# SUPI_MediumR2.net
KiCad netlist of a schematic drawn in Altium Designer
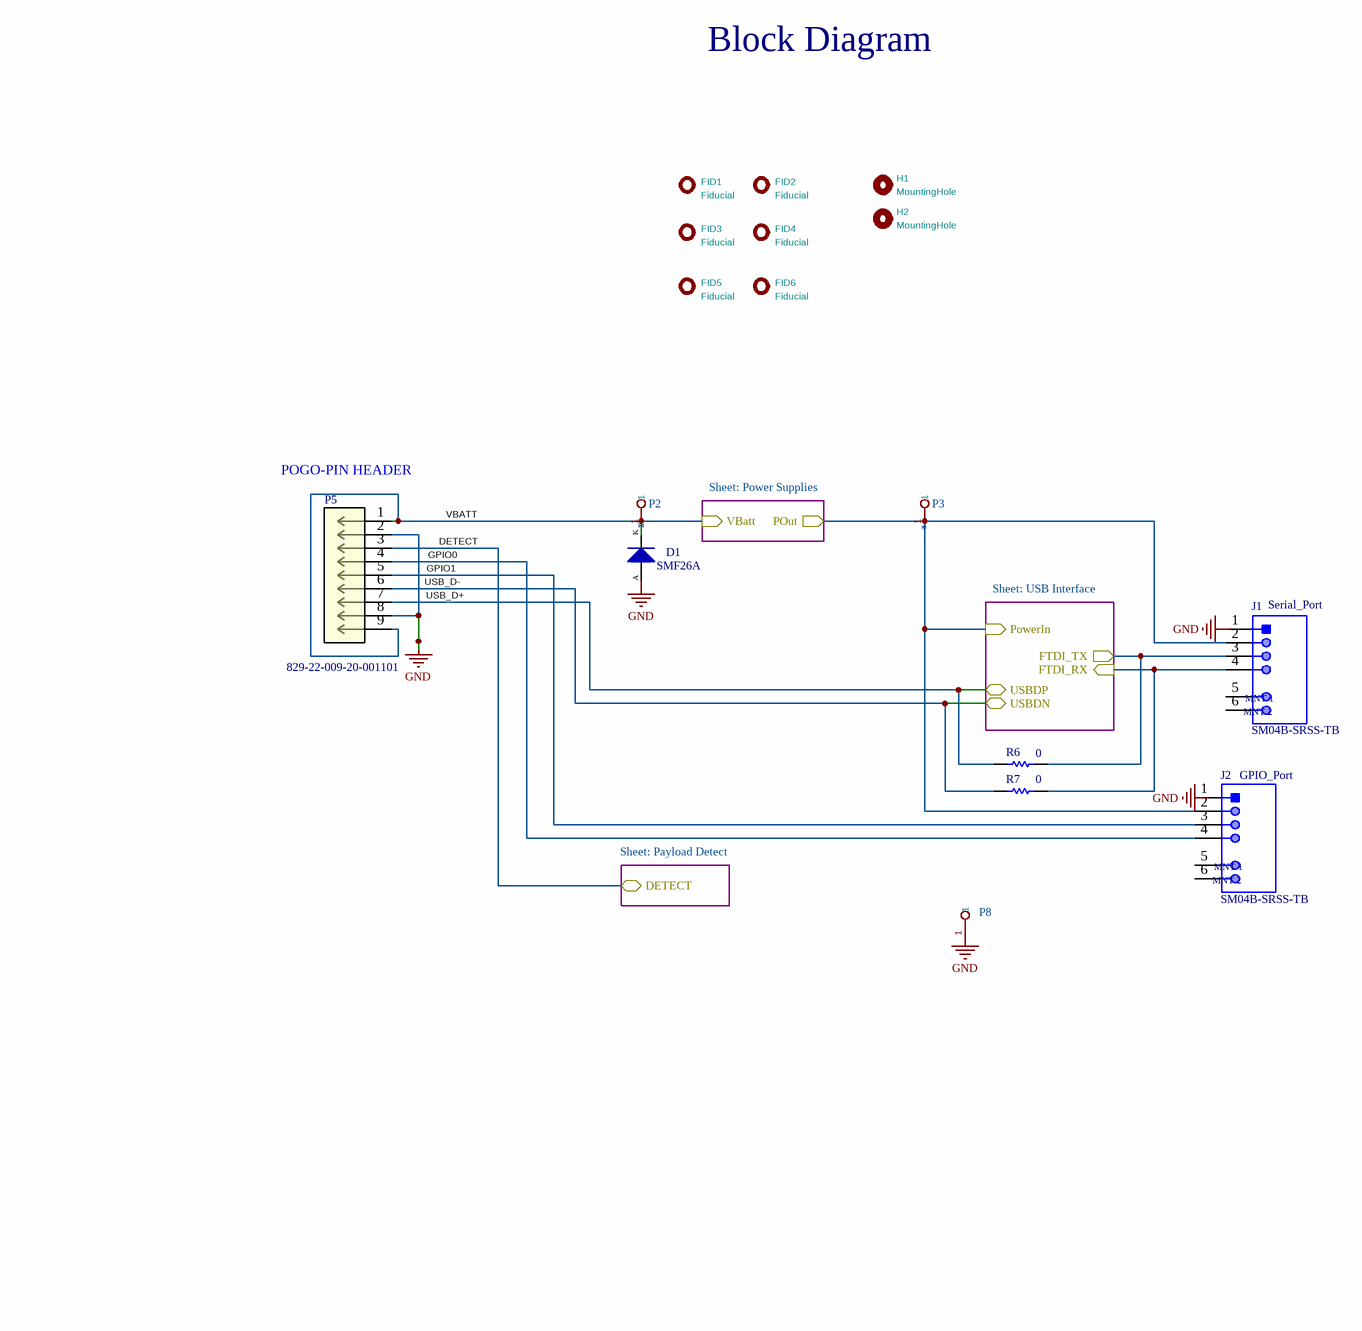
[diagram p0: SUPI_MediumR2.SchDoc]

(export (version "E")
  (design (tool "Eeschema 10.0.6"))
  (components
    (comp (ref "D1")
      (value "SMF26A")
      (footprint "DI-SOD123F-A")
      (description "SMF Series 200 W 26 V Uni-Directional Surface Mount TVS Diode - SOD-123F")
      (libsource (lib "Picatinny Server") (part "Diode"))
    )
    (comp (ref "FID1")
      (value "Fiducial")
      (footprint "Fiducial_Cu0.040_Mask0.060")
      (libsource (lib "1a_Misc") (part "Fiducial_40mil_mask_60mil"))
    )
    (comp (ref "FID2")
      (value "Fiducial")
      (footprint "Fiducial_Cu0.040_Mask0.060")
      (libsource (lib "1a_Misc") (part "Fiducial_40mil_mask_60mil"))
    )
    (comp (ref "FID3")
      (value "Fiducial")
      (footprint "Fiducial_Cu0.040_Mask0.060")
      (libsource (lib "1a_Misc") (part "Fiducial_40mil_mask_60mil"))
    )
    (comp (ref "FID4")
      (value "Fiducial")
      (footprint "Fiducial_Cu0.040_Mask0.060")
      (libsource (lib "1a_Misc") (part "Fiducial_40mil_mask_60mil"))
    )
    (comp (ref "FID5")
      (value "Fiducial")
      (footprint "Fiducial_Cu0.040_Mask0.060")
      (libsource (lib "1a_Misc") (part "Fiducial_40mil_mask_60mil"))
    )
    (comp (ref "FID6")
      (value "Fiducial")
      (footprint "Fiducial_Cu0.040_Mask0.060")
      (libsource (lib "1a_Misc") (part "Fiducial_40mil_mask_60mil"))
    )
    (comp (ref "H1")
      (value "MountingHole")
      (footprint "MountingHole_2.2mm_M2_DIN965")
      (libsource (lib "Mechanical") (part "MountingHole"))
    )
    (comp (ref "H2")
      (value "MountingHole")
      (footprint "MountingHole_2.2mm_M2_DIN965")
      (libsource (lib "Mechanical") (part "MountingHole"))
    )
    (comp (ref "J1")
      (value "SM04B-SRSS-TB")
      (footprint "SM04B-SRSS-TB")
      (description "Conn Shrouded Header (4 Sides) HDR 4 POS 1.25mm Solder RA Side Entry SMD T/R")
      (libsource (lib "Picatinny Server") (part "SM04B-GHS-TB"))
    )
    (comp (ref "J2")
      (value "SM04B-SRSS-TB")
      (footprint "SM04B-SRSS-TB")
      (description "Conn Shrouded Header (4 Sides) HDR 4 POS 1.25mm Solder RA Side Entry SMD T/R")
      (libsource (lib "Picatinny Server") (part "SM04B-GHS-TB"))
    )
    (comp (ref "P2")
      (value "*")
      (footprint "TP_SMD_1MM")
      (libsource (lib "1a_Misc") (part "Hand_Solder_Pad_100x80_mil"))
    )
    (comp (ref "P3")
      (value "*")
      (footprint "TP_SMD_1MM")
      (libsource (lib "1a_Misc") (part "Hand_Solder_Pad_100x80_mil"))
    )
    (comp (ref "P5")
      (value "829-22-009-20-001101")
      (footprint "829-22-009-20-001101")
      (description "Board Connector, 9 Contact(s), 1 Row(s), Male, Right Angle, Solder Terminal")
      (libsource (lib "Picatinny Server") (part "9 Pos Connector"))
    )
    (comp (ref "P8")
      (value "~")
      (footprint "TP_SMD_1MM")
      (libsource (lib "1a_Misc") (part "Hand_Solder_Pad_100x80_mil"))
    )
    (comp (ref "R6")
      (value "0")
      (footprint "RES-0402-A")
      (description "Res 0402 0 Ohm 1/16W 5% Thick Film")
      (libsource (lib "Picatinny Server") (part "Resistor"))
    )
    (comp (ref "R7")
      (value "0")
      (footprint "RES-0402-A")
      (description "Res 0402 0 Ohm 1/16W 5% Thick Film")
      (libsource (lib "Picatinny Server") (part "Resistor"))
    )
  )
  (nets
    (net (code "1") (name "/DETECT") (class "Default")
      (node (ref "P5") (pin "3") (pinfunction "3_3") (pintype "passive"))
    )
    (net (code "2") (name "/FTDI_RX") (class "Default")
      (node (ref "J1") (pin "4") (pinfunction "4_4") (pintype "passive"))
      (node (ref "R7") (pin "2") (pinfunction "2_2") (pintype "passive"))
    )
    (net (code "3") (name "/FTDI_TX") (class "Default")
      (node (ref "J1") (pin "3") (pinfunction "3_3") (pintype "passive"))
      (node (ref "R6") (pin "2") (pinfunction "2_2") (pintype "passive"))
    )
    (net (code "4") (name "/GPIO0") (class "Default")
      (node (ref "J2") (pin "4") (pinfunction "4_4") (pintype "passive"))
      (node (ref "P5") (pin "4") (pinfunction "4_4") (pintype "passive"))
    )
    (net (code "5") (name "/GPIO1") (class "Default")
      (node (ref "J2") (pin "3") (pinfunction "3_3") (pintype "passive"))
      (node (ref "P5") (pin "5") (pinfunction "5_5") (pintype "passive"))
    )
    (net (code "6") (name "/POut") (class "Default")
      (node (ref "J1") (pin "2") (pinfunction "2_2") (pintype "passive"))
      (node (ref "J2") (pin "2") (pinfunction "2_2") (pintype "passive"))
      (node (ref "P3") (pin "1") (pinfunction "1_1") (pintype "passive"))
    )
    (net (code "7") (name "/USB_D+") (class "Default")
      (node (ref "P5") (pin "7") (pinfunction "7_7") (pintype "passive"))
      (node (ref "R6") (pin "1") (pinfunction "1_1") (pintype "passive"))
    )
    (net (code "8") (name "/USB_D-") (class "Default")
      (node (ref "P5") (pin "6") (pinfunction "6_6") (pintype "passive"))
      (node (ref "R7") (pin "1") (pinfunction "1_1") (pintype "passive"))
    )
    (net (code "9") (name "/VBATT") (class "Default")
      (node (ref "D1") (pin "K") (pinfunction "K_K") (pintype "passive"))
      (node (ref "P2") (pin "1") (pinfunction "1_1") (pintype "passive"))
      (node (ref "P5") (pin "1") (pinfunction "1_1") (pintype "passive"))
      (node (ref "P5") (pin "9") (pinfunction "9_9") (pintype "passive"))
    )
    (net (code "10") (name "GND") (class "Default")
      (node (ref "P5") (pin "2") (pinfunction "2_2") (pintype "passive"))
      (node (ref "P5") (pin "8") (pinfunction "8_8") (pintype "passive"))
      (node (ref "P8") (pin "1") (pinfunction "1_1") (pintype "passive"))
    )
    (net (code "11") (name "unconnected-(D1-PadA)") (class "Default")
      (node (ref "D1") (pin "A") (pinfunction "A_A") (pintype "passive"))
    )
    (net (code "12") (name "unconnected-(J1-Pad1)") (class "Default")
      (node (ref "J1") (pin "1") (pinfunction "1_1") (pintype "passive"))
    )
    (net (code "13") (name "unconnected-(J1-Pad5)") (class "Default")
      (node (ref "J1") (pin "5") (pinfunction "5_5") (pintype "passive"))
    )
    (net (code "14") (name "unconnected-(J1-Pad6)") (class "Default")
      (node (ref "J1") (pin "6") (pinfunction "6_6") (pintype "passive"))
    )
    (net (code "15") (name "unconnected-(J2-Pad1)") (class "Default")
      (node (ref "J2") (pin "1") (pinfunction "1_1") (pintype "passive"))
    )
    (net (code "16") (name "unconnected-(J2-Pad5)") (class "Default")
      (node (ref "J2") (pin "5") (pinfunction "5_5") (pintype "passive"))
    )
    (net (code "17") (name "unconnected-(J2-Pad6)") (class "Default")
      (node (ref "J2") (pin "6") (pinfunction "6_6") (pintype "passive"))
    )
  )
)
